# RemoteSwitch.net
KiCad netlist of a schematic drawn in Altium Designer
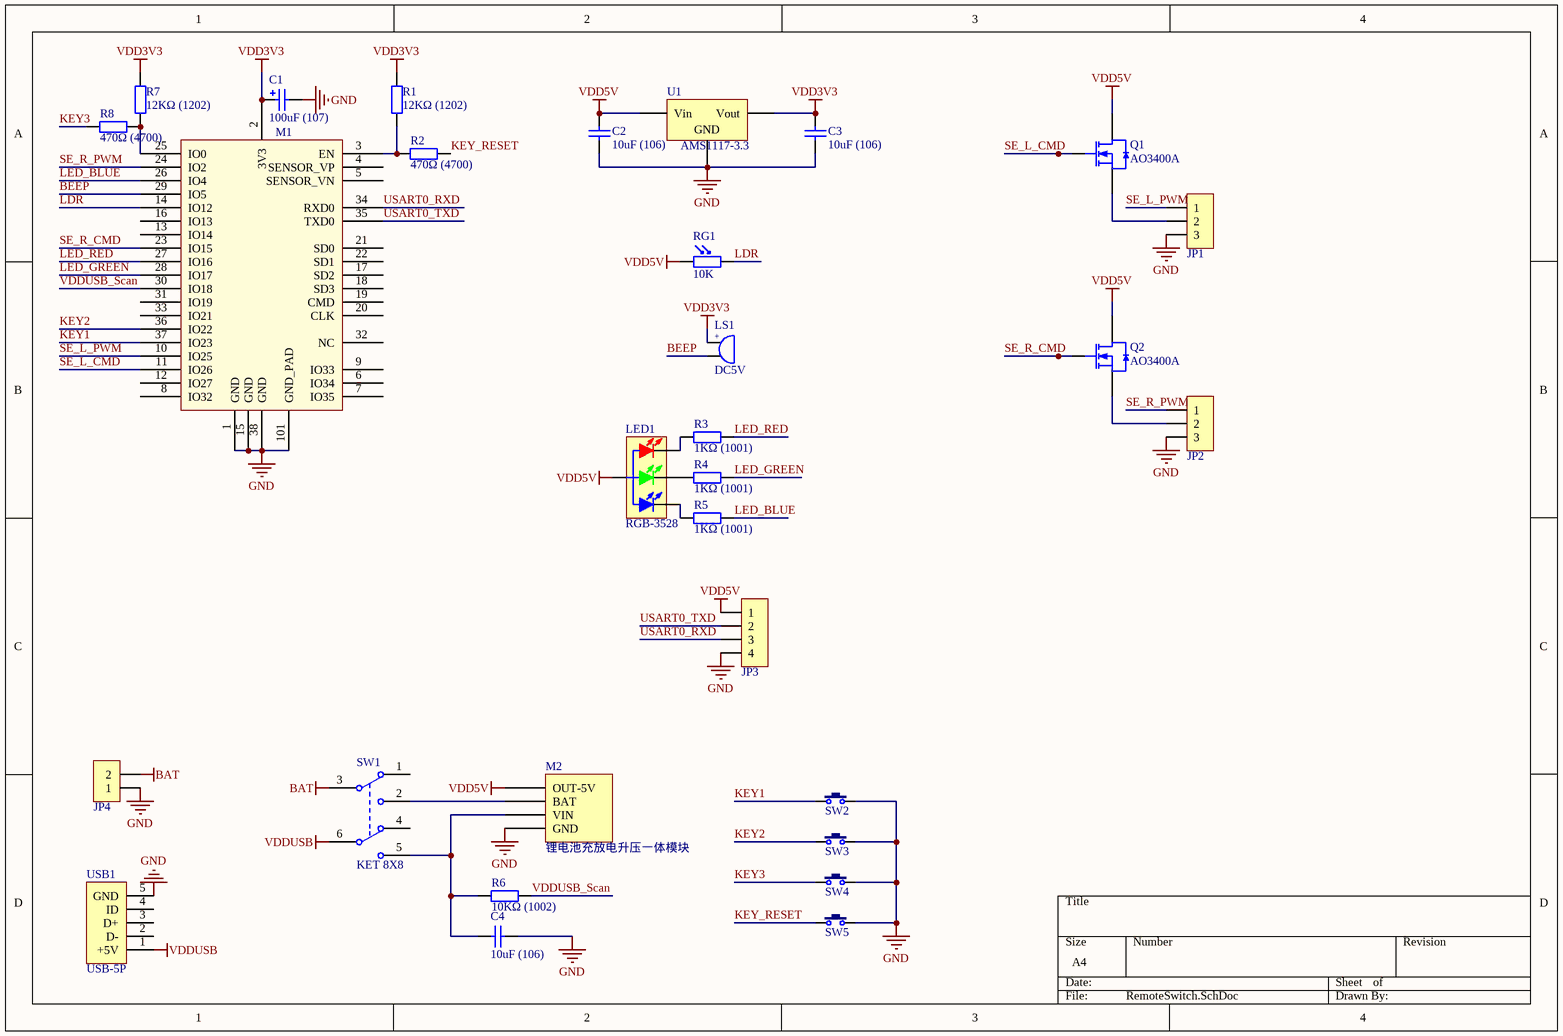
[diagram p0: RemoteSwitch.SchDoc]

(export (version "E")
  (design (tool "Eeschema 10.0.6"))
  (components
    (comp (ref "C1")
      (value "100uF (107)")
      (footprint "CASE-B_3528")
      (description "钽电容")
      (libsource (lib "Miscellaneous Devices LC") (part "3528 100uF (107) 10% 6.3V"))
    )
    (comp (ref "C2")
      (value "10uF (106)")
      (footprint "0805_C")
      (description "贴片电容")
      (libsource (lib "Miscellaneous Devices LC") (part "0805 10uF (106) 10% 25V"))
    )
    (comp (ref "C3")
      (value "10uF (106)")
      (footprint "0805_C")
      (description "贴片电容")
      (libsource (lib "Miscellaneous Devices LC") (part "0805 10uF (106) 10% 25V"))
    )
    (comp (ref "C4")
      (value "10uF (106)")
      (footprint "0805_C")
      (description "贴片电容")
      (libsource (lib "Miscellaneous Devices LC") (part "0805 10uF (106) 10% 25V"))
    )
    (comp (ref "JP1")
      (value "HDR-1X3")
      (footprint "HDR2.54-LI-3P")
      (description "3P接插件")
      (libsource (lib "5.3 - 接插件-脚距2.54 (100mil) ") (part "Header 3"))
    )
    (comp (ref "JP2")
      (value "HDR-1X3")
      (footprint "HDR2.54-LI-3P")
      (description "3P接插件")
      (libsource (lib "5.3 - 接插件-脚距2.54 (100mil) ") (part "Header 3"))
    )
    (comp (ref "JP3")
      (value "HDR-1X4")
      (footprint "HDR2.54-LI-4P")
      (description "4P接插件")
      (libsource (lib "5.3 - 接插件-脚距2.54 (100mil) ") (part "Header 4"))
    )
    (comp (ref "JP4")
      (value "HDR-1X2")
      (footprint "HDR2.54-LI-2P")
      (description "2P接插件")
      (libsource (lib "5.3 - 接插件-脚距2.54 (100mil) ") (part "Header 2"))
    )
    (comp (ref "LED1")
      (value "RGB-3528")
      (footprint "LED 3528-4Pin")
      (description "3528三基色LED")
      (libsource (lib "0.3 - LED发光二极管") (part "LED-RGB 3528"))
    )
    (comp (ref "LS1")
      (value "DC5V")
      (footprint "BEEP 5x9x5.5")
      (description "蜂鸣器")
      (libsource (lib "4.1 - 未分类器件") (part "BEEP"))
    )
    (comp (ref "M1")
      (value "ESP-32S_Module")
      (footprint "ESP32S")
      (description "Esp-32S")
      (libsource (lib "ESP32S") (part "ESP32S_Module"))
    )
    (comp (ref "M2")
      (value "锂电池充放电升压一体模块")
      (footprint "PCBComponent_1")
      (libsource (lib "XTZ常用元器件库") (part "锂电池充放电升压一体模块"))
    )
    (comp (ref "Q1")
      (value "AO3400A")
      (footprint "SOT-23-3L")
      (description "MOS(场效应管)")
      (libsource (lib "Miscellaneous Devices LC") (part "AO3400A N道沟 X0YV1T SOT-23"))
    )
    (comp (ref "Q2")
      (value "AO3400A")
      (footprint "SOT-23-3L")
      (description "MOS(场效应管)")
      (libsource (lib "Miscellaneous Devices LC") (part "AO3400A N道沟 X0YV1T SOT-23"))
    )
    (comp (ref "R1")
      (value "12KΩ (1202)")
      (footprint "0805_R")
      (description "贴片电阻")
      (libsource (lib "Miscellaneous Devices LC") (part "0805 12KΩ (1202) 1%"))
    )
    (comp (ref "R2")
      (value "470Ω (4700)")
      (footprint "0805_R")
      (description "贴片电阻")
      (libsource (lib "Miscellaneous Devices LC") (part "0805 470Ω (4700) 1%"))
    )
    (comp (ref "R3")
      (value "1KΩ (1001)")
      (footprint "0805_R")
      (description "贴片电阻")
      (libsource (lib "Miscellaneous Devices LC") (part "0805 1KΩ (1001) 1%"))
    )
    (comp (ref "R4")
      (value "1KΩ (1001)")
      (footprint "0805_R")
      (description "贴片电阻")
      (libsource (lib "Miscellaneous Devices LC") (part "0805 1KΩ (1001) 1%"))
    )
    (comp (ref "R5")
      (value "1KΩ (1001)")
      (footprint "0805_R")
      (description "贴片电阻")
      (libsource (lib "Miscellaneous Devices LC") (part "0805 1KΩ (1001) 1%"))
    )
    (comp (ref "R6")
      (value "10KΩ (1002)")
      (footprint "0805_R")
      (description "贴片电阻")
      (libsource (lib "Miscellaneous Devices LC") (part "0805 10KΩ (1002) 1%"))
    )
    (comp (ref "R7")
      (value "12KΩ (1202)")
      (footprint "0805_R")
      (description "贴片电阻")
      (libsource (lib "Miscellaneous Devices LC") (part "0805 12KΩ (1202) 1%"))
    )
    (comp (ref "R8")
      (value "470Ω (4700)")
      (footprint "0805_R")
      (description "贴片电阻")
      (libsource (lib "Miscellaneous Devices LC") (part "0805 470Ω (4700) 1%"))
    )
    (comp (ref "RG1")
      (value "10K")
      (footprint "RG5528")
      (description "光敏电阻")
      (libsource (lib "0.1 - 电阻-电容-电感") (part "RG"))
    )
    (comp (ref "SW1")
      (value "KET 8X8")
      (footprint "KFT DIP-8X8")
      (description "8*8自锁开关")
      (libsource (lib "0.7 - 常用按键-开关") (part "KET 8X8"))
    )
    (comp (ref "SW2")
      (value "6x6x5")
      (footprint "TSW DIP-6*6*6_V")
      (description "侧按直插6x6轻触开关")
      (libsource (lib "0.7 - 常用按键-开关") (part "TSW DIP-6x6_V"))
    )
    (comp (ref "SW3")
      (value "6x6x5")
      (footprint "TSW DIP-6*6*6_V")
      (description "侧按直插6x6轻触开关")
      (libsource (lib "0.7 - 常用按键-开关") (part "TSW DIP-6x6_V"))
    )
    (comp (ref "SW4")
      (value "6x6x5")
      (footprint "TSW DIP-6*6*6_V")
      (description "侧按直插6x6轻触开关")
      (libsource (lib "0.7 - 常用按键-开关") (part "TSW DIP-6x6_V"))
    )
    (comp (ref "SW5")
      (value "6x6x5")
      (footprint "TSW DIP-6*6*6_V")
      (description "侧按直插6x6轻触开关")
      (libsource (lib "0.7 - 常用按键-开关") (part "TSW DIP-6x6_V"))
    )
    (comp (ref "U1")
      (value "AMS1117-3.3")
      (footprint "SOT-223")
      (description "低压差线性稳压(LDO)")
      (libsource (lib "Miscellaneous Devices LC") (part "SOT-223 AMS1117-3.3"))
    )
    (comp (ref "USB1")
      (value "USB-5P")
      (footprint "USB-MICRO_A")
      (description "微型USB母座")
      (libsource (lib "0.8 - 以太网-音频-USB插座") (part "USB-5P"))
    )
  )
  (nets
    (net (code "1") (name "/BEEP") (class "Default")
      (node (ref "LS1") (pin "2") (pinfunction "2_2") (pintype "passive"))
      (node (ref "M1") (pin "29") (pinfunction "IO5_29") (pintype "passive"))
    )
    (net (code "2") (name "/KEY1") (class "Default")
      (node (ref "M1") (pin "37") (pinfunction "IO23_37") (pintype "passive"))
      (node (ref "SW2") (pin "1") (pinfunction "1_1") (pintype "passive"))
    )
    (net (code "3") (name "/KEY2") (class "Default")
      (node (ref "M1") (pin "36") (pinfunction "IO22_36") (pintype "passive"))
      (node (ref "SW3") (pin "1") (pinfunction "1_1") (pintype "passive"))
    )
    (net (code "4") (name "/KEY3") (class "Default")
      (node (ref "R8") (pin "2") (pinfunction "2_2") (pintype "passive"))
      (node (ref "SW4") (pin "1") (pinfunction "1_1") (pintype "passive"))
    )
    (net (code "5") (name "/KEY_RESET") (class "Default")
      (node (ref "R2") (pin "1") (pinfunction "1_1") (pintype "passive"))
      (node (ref "SW5") (pin "1") (pinfunction "1_1") (pintype "passive"))
    )
    (net (code "6") (name "/LDR") (class "Default")
      (node (ref "M1") (pin "14") (pinfunction "IO12_14") (pintype "passive"))
      (node (ref "RG1") (pin "2") (pinfunction "2_2") (pintype "passive"))
    )
    (net (code "7") (name "/LED_BLUE") (class "Default")
      (node (ref "M1") (pin "26") (pinfunction "IO4_26") (pintype "passive"))
      (node (ref "R5") (pin "1") (pinfunction "1_1") (pintype "passive"))
    )
    (net (code "8") (name "/LED_GREEN") (class "Default")
      (node (ref "M1") (pin "28") (pinfunction "IO17_28") (pintype "passive"))
      (node (ref "R4") (pin "1") (pinfunction "1_1") (pintype "passive"))
    )
    (net (code "9") (name "/LED_RED") (class "Default")
      (node (ref "M1") (pin "27") (pinfunction "IO16_27") (pintype "passive"))
      (node (ref "R3") (pin "1") (pinfunction "1_1") (pintype "passive"))
    )
    (net (code "10") (name "/SE_L_CMD") (class "Default")
      (node (ref "M1") (pin "11") (pinfunction "IO26_11") (pintype "passive"))
      (node (ref "Q1") (pin "1") (pinfunction "G_1") (pintype "passive"))
    )
    (net (code "11") (name "/SE_L_PWM") (class "Default")
      (node (ref "JP1") (pin "1") (pinfunction "1_1") (pintype "passive"))
      (node (ref "M1") (pin "10") (pinfunction "IO25_10") (pintype "passive"))
    )
    (net (code "12") (name "/SE_R_CMD") (class "Default")
      (node (ref "M1") (pin "23") (pinfunction "IO15_23") (pintype "passive"))
      (node (ref "Q2") (pin "1") (pinfunction "G_1") (pintype "passive"))
    )
    (net (code "13") (name "/SE_R_PWM") (class "Default")
      (node (ref "JP2") (pin "1") (pinfunction "1_1") (pintype "passive"))
      (node (ref "M1") (pin "24") (pinfunction "IO2_24") (pintype "passive"))
    )
    (net (code "14") (name "/USART0_RXD") (class "Default")
      (node (ref "JP3") (pin "3") (pinfunction "3_3") (pintype "passive"))
      (node (ref "M1") (pin "34") (pinfunction "RXD0_34") (pintype "passive"))
    )
    (net (code "15") (name "/USART0_TXD") (class "Default")
      (node (ref "JP3") (pin "2") (pinfunction "2_2") (pintype "passive"))
      (node (ref "M1") (pin "35") (pinfunction "TXD0_35") (pintype "passive"))
    )
    (net (code "16") (name "/VDDUSB_Scan") (class "Default")
      (node (ref "M1") (pin "30") (pinfunction "IO18_30") (pintype "passive"))
      (node (ref "R6") (pin "1") (pinfunction "1_1") (pintype "passive"))
    )
    (net (code "17") (name "BAT") (class "Default")
      (node (ref "JP4") (pin "2") (pinfunction "2_2") (pintype "passive"))
      (node (ref "SW1") (pin "3") (pinfunction "NO1_3") (pintype "passive"))
    )
    (net (code "18") (name "GND") (class "Default")
      (node (ref "C1") (pin "2") (pinfunction "2_2") (pintype "passive"))
      (node (ref "C2") (pin "1") (pinfunction "1_1") (pintype "passive"))
      (node (ref "C3") (pin "1") (pinfunction "1_1") (pintype "passive"))
      (node (ref "C4") (pin "1") (pinfunction "1_1") (pintype "passive"))
      (node (ref "JP1") (pin "3") (pinfunction "3_3") (pintype "passive"))
      (node (ref "JP2") (pin "3") (pinfunction "3_3") (pintype "passive"))
      (node (ref "JP3") (pin "4") (pinfunction "4_4") (pintype "passive"))
      (node (ref "JP4") (pin "1") (pinfunction "1_1") (pintype "passive"))
      (node (ref "M1") (pin "1") (pinfunction "GND_1") (pintype "power_in"))
      (node (ref "M1") (pin "101") (pinfunction "GND_PAD_101") (pintype "power_in"))
      (node (ref "M1") (pin "15") (pinfunction "GND_15") (pintype "power_in"))
      (node (ref "M1") (pin "38") (pinfunction "GND_38") (pintype "power_in"))
      (node (ref "M2") (pin "GND") (pinfunction "GND_GND") (pintype "passive"))
      (node (ref "SW2") (pin "2") (pinfunction "2_2") (pintype "passive"))
      (node (ref "SW3") (pin "2") (pinfunction "2_2") (pintype "passive"))
      (node (ref "SW4") (pin "2") (pinfunction "2_2") (pintype "passive"))
      (node (ref "SW5") (pin "2") (pinfunction "2_2") (pintype "passive"))
      (node (ref "U1") (pin "1") (pinfunction "GND_1") (pintype "passive"))
      (node (ref "USB1") (pin "5") (pinfunction "GND_5") (pintype "passive"))
    )
    (net (code "19") (name "Net-(C4-Pad2)") (class "Default")
      (node (ref "C4") (pin "2") (pinfunction "2_2") (pintype "passive"))
      (node (ref "M2") (pin "VIN") (pinfunction "VIN_VIN") (pintype "passive"))
      (node (ref "R6") (pin "2") (pinfunction "2_2") (pintype "passive"))
      (node (ref "SW1") (pin "5") (pinfunction "COM2_5") (pintype "passive"))
    )
    (net (code "20") (name "Net-(LED1-BULE_K)") (class "Default")
      (node (ref "LED1") (pin "3") (pinfunction "BULE_K_3") (pintype "passive"))
      (node (ref "R5") (pin "2") (pinfunction "2_2") (pintype "passive"))
    )
    (net (code "21") (name "Net-(LED1-GREEN_K)") (class "Default")
      (node (ref "LED1") (pin "2") (pinfunction "GREEN_K_2") (pintype "passive"))
      (node (ref "R4") (pin "2") (pinfunction "2_2") (pintype "passive"))
    )
    (net (code "22") (name "Net-(LED1-RED_K)") (class "Default")
      (node (ref "LED1") (pin "1") (pinfunction "RED_K_1") (pintype "passive"))
      (node (ref "R3") (pin "2") (pinfunction "2_2") (pintype "passive"))
    )
    (net (code "23") (name "Net-(M1-EN)") (class "Default")
      (node (ref "M1") (pin "3") (pinfunction "EN_3") (pintype "power_in"))
      (node (ref "R1") (pin "1") (pinfunction "1_1") (pintype "passive"))
      (node (ref "R2") (pin "2") (pinfunction "2_2") (pintype "passive"))
    )
    (net (code "24") (name "Net-(M1-IO0)") (class "Default")
      (node (ref "M1") (pin "25") (pinfunction "IO0_25") (pintype "passive"))
      (node (ref "R7") (pin "1") (pinfunction "1_1") (pintype "passive"))
      (node (ref "R8") (pin "1") (pinfunction "1_1") (pintype "passive"))
    )
    (net (code "25") (name "Net-(M2-PadBAT)") (class "Default")
      (node (ref "M2") (pin "BAT") (pinfunction "BAT_BAT") (pintype "passive"))
      (node (ref "SW1") (pin "2") (pinfunction "COM2_2") (pintype "passive"))
    )
    (net (code "26") (name "Net-(Q1-S)") (class "Default")
      (node (ref "JP1") (pin "2") (pinfunction "2_2") (pintype "passive"))
      (node (ref "Q1") (pin "2") (pinfunction "S_2") (pintype "passive"))
    )
    (net (code "27") (name "Net-(Q2-S)") (class "Default")
      (node (ref "JP2") (pin "2") (pinfunction "2_2") (pintype "passive"))
      (node (ref "Q2") (pin "2") (pinfunction "S_2") (pintype "passive"))
    )
    (net (code "28") (name "VDD3V3") (class "Default")
      (node (ref "C1") (pin "1") (pinfunction "1_1") (pintype "passive"))
      (node (ref "C3") (pin "2") (pinfunction "2_2") (pintype "passive"))
      (node (ref "LS1") (pin "1") (pinfunction "1_1") (pintype "passive"))
      (node (ref "M1") (pin "2") (pinfunction "3V3_2") (pintype "power_in"))
      (node (ref "R1") (pin "2") (pinfunction "2_2") (pintype "passive"))
      (node (ref "R7") (pin "2") (pinfunction "2_2") (pintype "passive"))
      (node (ref "U1") (pin "2") (pinfunction "Vout_2") (pintype "passive"))
    )
    (net (code "29") (name "VDD5V") (class "Default")
      (node (ref "C2") (pin "2") (pinfunction "2_2") (pintype "passive"))
      (node (ref "JP3") (pin "1") (pinfunction "1_1") (pintype "passive"))
      (node (ref "LED1") (pin "4") (pinfunction "A_4") (pintype "passive"))
      (node (ref "M2") (pin "OUT-5V") (pinfunction "OUT-5V_OUT-5V") (pintype "passive"))
      (node (ref "Q1") (pin "3") (pinfunction "D_3") (pintype "passive"))
      (node (ref "Q2") (pin "3") (pinfunction "D_3") (pintype "passive"))
      (node (ref "RG1") (pin "1") (pinfunction "1_1") (pintype "passive"))
      (node (ref "U1") (pin "3") (pinfunction "Vin_3") (pintype "passive"))
    )
    (net (code "30") (name "VDDUSB") (class "Default")
      (node (ref "SW1") (pin "6") (pinfunction "NC2_6") (pintype "passive"))
      (node (ref "USB1") (pin "1") (pinfunction "+5V_1") (pintype "passive"))
    )
    (net (code "31") (name "unconnected-(M1-CLK-Pad20)") (class "Default")
      (node (ref "M1") (pin "20") (pinfunction "CLK_20") (pintype "passive"))
    )
    (net (code "32") (name "unconnected-(M1-CMD-Pad19)") (class "Default")
      (node (ref "M1") (pin "19") (pinfunction "CMD_19") (pintype "passive"))
    )
    (net (code "33") (name "unconnected-(M1-IO13-Pad16)") (class "Default")
      (node (ref "M1") (pin "16") (pinfunction "IO13_16") (pintype "passive"))
    )
    (net (code "34") (name "unconnected-(M1-IO14-Pad13)") (class "Default")
      (node (ref "M1") (pin "13") (pinfunction "IO14_13") (pintype "passive"))
    )
    (net (code "35") (name "unconnected-(M1-IO19-Pad31)") (class "Default")
      (node (ref "M1") (pin "31") (pinfunction "IO19_31") (pintype "passive"))
    )
    (net (code "36") (name "unconnected-(M1-IO21-Pad33)") (class "Default")
      (node (ref "M1") (pin "33") (pinfunction "IO21_33") (pintype "passive"))
    )
    (net (code "37") (name "unconnected-(M1-IO27-Pad12)") (class "Default")
      (node (ref "M1") (pin "12") (pinfunction "IO27_12") (pintype "passive"))
    )
    (net (code "38") (name "unconnected-(M1-IO32-Pad8)") (class "Default")
      (node (ref "M1") (pin "8") (pinfunction "IO32_8") (pintype "passive"))
    )
    (net (code "39") (name "unconnected-(M1-IO33-Pad9)") (class "Default")
      (node (ref "M1") (pin "9") (pinfunction "IO33_9") (pintype "passive"))
    )
    (net (code "40") (name "unconnected-(M1-IO34-Pad6)") (class "Default")
      (node (ref "M1") (pin "6") (pinfunction "IO34_6") (pintype "passive"))
    )
    (net (code "41") (name "unconnected-(M1-IO35-Pad7)") (class "Default")
      (node (ref "M1") (pin "7") (pinfunction "IO35_7") (pintype "passive"))
    )
    (net (code "42") (name "unconnected-(M1-NC-Pad32)") (class "Default")
      (node (ref "M1") (pin "32") (pinfunction "NC_32") (pintype "passive"))
    )
    (net (code "43") (name "unconnected-(M1-SD0-Pad21)") (class "Default")
      (node (ref "M1") (pin "21") (pinfunction "SD0_21") (pintype "passive"))
    )
    (net (code "44") (name "unconnected-(M1-SD1-Pad22)") (class "Default")
      (node (ref "M1") (pin "22") (pinfunction "SD1_22") (pintype "passive"))
    )
    (net (code "45") (name "unconnected-(M1-SD2-Pad17)") (class "Default")
      (node (ref "M1") (pin "17") (pinfunction "SD2_17") (pintype "passive"))
    )
    (net (code "46") (name "unconnected-(M1-SD3-Pad18)") (class "Default")
      (node (ref "M1") (pin "18") (pinfunction "SD3_18") (pintype "passive"))
    )
    (net (code "47") (name "unconnected-(M1-SENSOR_VN-Pad5)") (class "Default")
      (node (ref "M1") (pin "5") (pinfunction "SENSOR_VN_5") (pintype "passive"))
    )
    (net (code "48") (name "unconnected-(M1-SENSOR_VP-Pad4)") (class "Default")
      (node (ref "M1") (pin "4") (pinfunction "SENSOR_VP_4") (pintype "passive"))
    )
    (net (code "49") (name "unconnected-(SW1-NC1-Pad1)") (class "Default")
      (node (ref "SW1") (pin "1") (pinfunction "NC1_1") (pintype "passive"))
    )
    (net (code "50") (name "unconnected-(SW1-NO2-Pad4)") (class "Default")
      (node (ref "SW1") (pin "4") (pinfunction "NO2_4") (pintype "passive"))
    )
    (net (code "51") (name "unconnected-(USB1-D+-Pad3)") (class "Default")
      (node (ref "USB1") (pin "3") (pinfunction "D+_3") (pintype "passive"))
    )
    (net (code "52") (name "unconnected-(USB1-D--Pad2)") (class "Default")
      (node (ref "USB1") (pin "2") (pinfunction "D-_2") (pintype "passive"))
    )
    (net (code "53") (name "unconnected-(USB1-ID-Pad4)") (class "Default")
      (node (ref "USB1") (pin "4") (pinfunction "ID_4") (pintype "passive"))
    )
  )
)
